# lixie_digit_dots.net
KiCad netlist of a schematic drawn in EAGLE
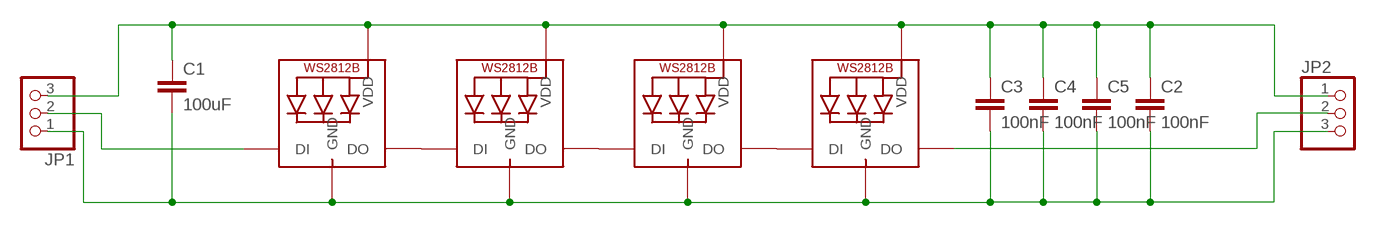
[diagram p0: schematic, sheet 1]

(export (version "E")
  (design (tool "Eeschema 10.0.6"))
  (components
    (comp (ref "C1")
      (value "100uF")
      (footprint "eagle-import:C1206K")
      (libsource (lib "eagle-import") (part "C-EUC1206K"))
    )
    (comp (ref "C2")
      (value "100nF")
      (footprint "eagle-import:C0402K")
      (libsource (lib "eagle-import") (part "C-EUC0402K"))
    )
    (comp (ref "C3")
      (value "100nF")
      (footprint "eagle-import:C0402K")
      (libsource (lib "eagle-import") (part "C-EUC0402K"))
    )
    (comp (ref "C4")
      (value "100nF")
      (footprint "eagle-import:C0402K")
      (libsource (lib "eagle-import") (part "C-EUC0402K"))
    )
    (comp (ref "C5")
      (value "100nF")
      (footprint "eagle-import:C0402K")
      (libsource (lib "eagle-import") (part "C-EUC0402K"))
    )
    (comp (ref "JP1")
      (value "PINHD-1X3")
      (footprint "eagle-import:1X03")
      (libsource (lib "eagle-import") (part "PINHD-1X3"))
    )
    (comp (ref "JP2")
      (value "PINHD-1X3")
      (footprint "eagle-import:1X03")
      (libsource (lib "eagle-import") (part "PINHD-1X3"))
    )
    (comp (ref "LED1")
      (value "WS2812B5050")
      (footprint "eagle-import:WS2812B")
      (libsource (lib "eagle-import") (part "WS2812B5050"))
    )
    (comp (ref "LED2")
      (value "WS2812B5050")
      (footprint "eagle-import:WS2812B")
      (libsource (lib "eagle-import") (part "WS2812B5050"))
    )
    (comp (ref "LED3")
      (value "WS2812B5050")
      (footprint "eagle-import:WS2812B")
      (libsource (lib "eagle-import") (part "WS2812B5050"))
    )
    (comp (ref "LED4")
      (value "WS2812B5050")
      (footprint "eagle-import:WS2812B")
      (libsource (lib "eagle-import") (part "WS2812B5050"))
    )
  )
  (nets
    (net (code "1") (name "Net-(LED1-DI)") (class "Default")
      (node (ref "JP1") (pin "2") (pinfunction "2_2") (pintype "passive"))
      (node (ref "LED1") (pin "4-DIN") (pinfunction "DI_4-DIN") (pintype "input"))
    )
    (net (code "2") (name "Net-(LED1-DO)") (class "Default")
      (node (ref "LED1") (pin "2-DOUT") (pinfunction "DO_2-DOUT") (pintype "output"))
      (node (ref "LED2") (pin "4-DIN") (pinfunction "DI_4-DIN") (pintype "input"))
    )
    (net (code "3") (name "Net-(LED1-GND)") (class "Default")
      (node (ref "C1") (pin "2") (pinfunction "2_2") (pintype "passive"))
      (node (ref "C2") (pin "2") (pinfunction "2_2") (pintype "passive"))
      (node (ref "C3") (pin "2") (pinfunction "2_2") (pintype "passive"))
      (node (ref "C4") (pin "2") (pinfunction "2_2") (pintype "passive"))
      (node (ref "C5") (pin "2") (pinfunction "2_2") (pintype "passive"))
      (node (ref "JP1") (pin "1") (pinfunction "1_1") (pintype "passive"))
      (node (ref "JP2") (pin "3") (pinfunction "3_3") (pintype "passive"))
      (node (ref "LED1") (pin "3-GND") (pinfunction "GND_3-GND") (pintype "power_in"))
      (node (ref "LED2") (pin "3-GND") (pinfunction "GND_3-GND") (pintype "power_in"))
      (node (ref "LED3") (pin "3-GND") (pinfunction "GND_3-GND") (pintype "power_in"))
      (node (ref "LED4") (pin "3-GND") (pinfunction "GND_3-GND") (pintype "power_in"))
    )
    (net (code "4") (name "Net-(LED1-VDD)") (class "Default")
      (node (ref "C1") (pin "1") (pinfunction "1_1") (pintype "passive"))
      (node (ref "C2") (pin "1") (pinfunction "1_1") (pintype "passive"))
      (node (ref "C3") (pin "1") (pinfunction "1_1") (pintype "passive"))
      (node (ref "C4") (pin "1") (pinfunction "1_1") (pintype "passive"))
      (node (ref "C5") (pin "1") (pinfunction "1_1") (pintype "passive"))
      (node (ref "JP1") (pin "3") (pinfunction "3_3") (pintype "passive"))
      (node (ref "JP2") (pin "1") (pinfunction "1_1") (pintype "passive"))
      (node (ref "LED1") (pin "1-VDD") (pinfunction "VDD_1-VDD") (pintype "power_in"))
      (node (ref "LED2") (pin "1-VDD") (pinfunction "VDD_1-VDD") (pintype "power_in"))
      (node (ref "LED3") (pin "1-VDD") (pinfunction "VDD_1-VDD") (pintype "power_in"))
      (node (ref "LED4") (pin "1-VDD") (pinfunction "VDD_1-VDD") (pintype "power_in"))
    )
    (net (code "5") (name "Net-(LED2-DO)") (class "Default")
      (node (ref "LED2") (pin "2-DOUT") (pinfunction "DO_2-DOUT") (pintype "output"))
      (node (ref "LED3") (pin "4-DIN") (pinfunction "DI_4-DIN") (pintype "input"))
    )
    (net (code "6") (name "Net-(LED3-DO)") (class "Default")
      (node (ref "LED3") (pin "2-DOUT") (pinfunction "DO_2-DOUT") (pintype "output"))
      (node (ref "LED4") (pin "4-DIN") (pinfunction "DI_4-DIN") (pintype "input"))
    )
    (net (code "7") (name "Net-(LED4-DO)") (class "Default")
      (node (ref "JP2") (pin "2") (pinfunction "2_2") (pintype "passive"))
      (node (ref "LED4") (pin "2-DOUT") (pinfunction "DO_2-DOUT") (pintype "output"))
    )
  )
)
